# thresholdboard.net
KiCad netlist of a schematic drawn in EAGLE
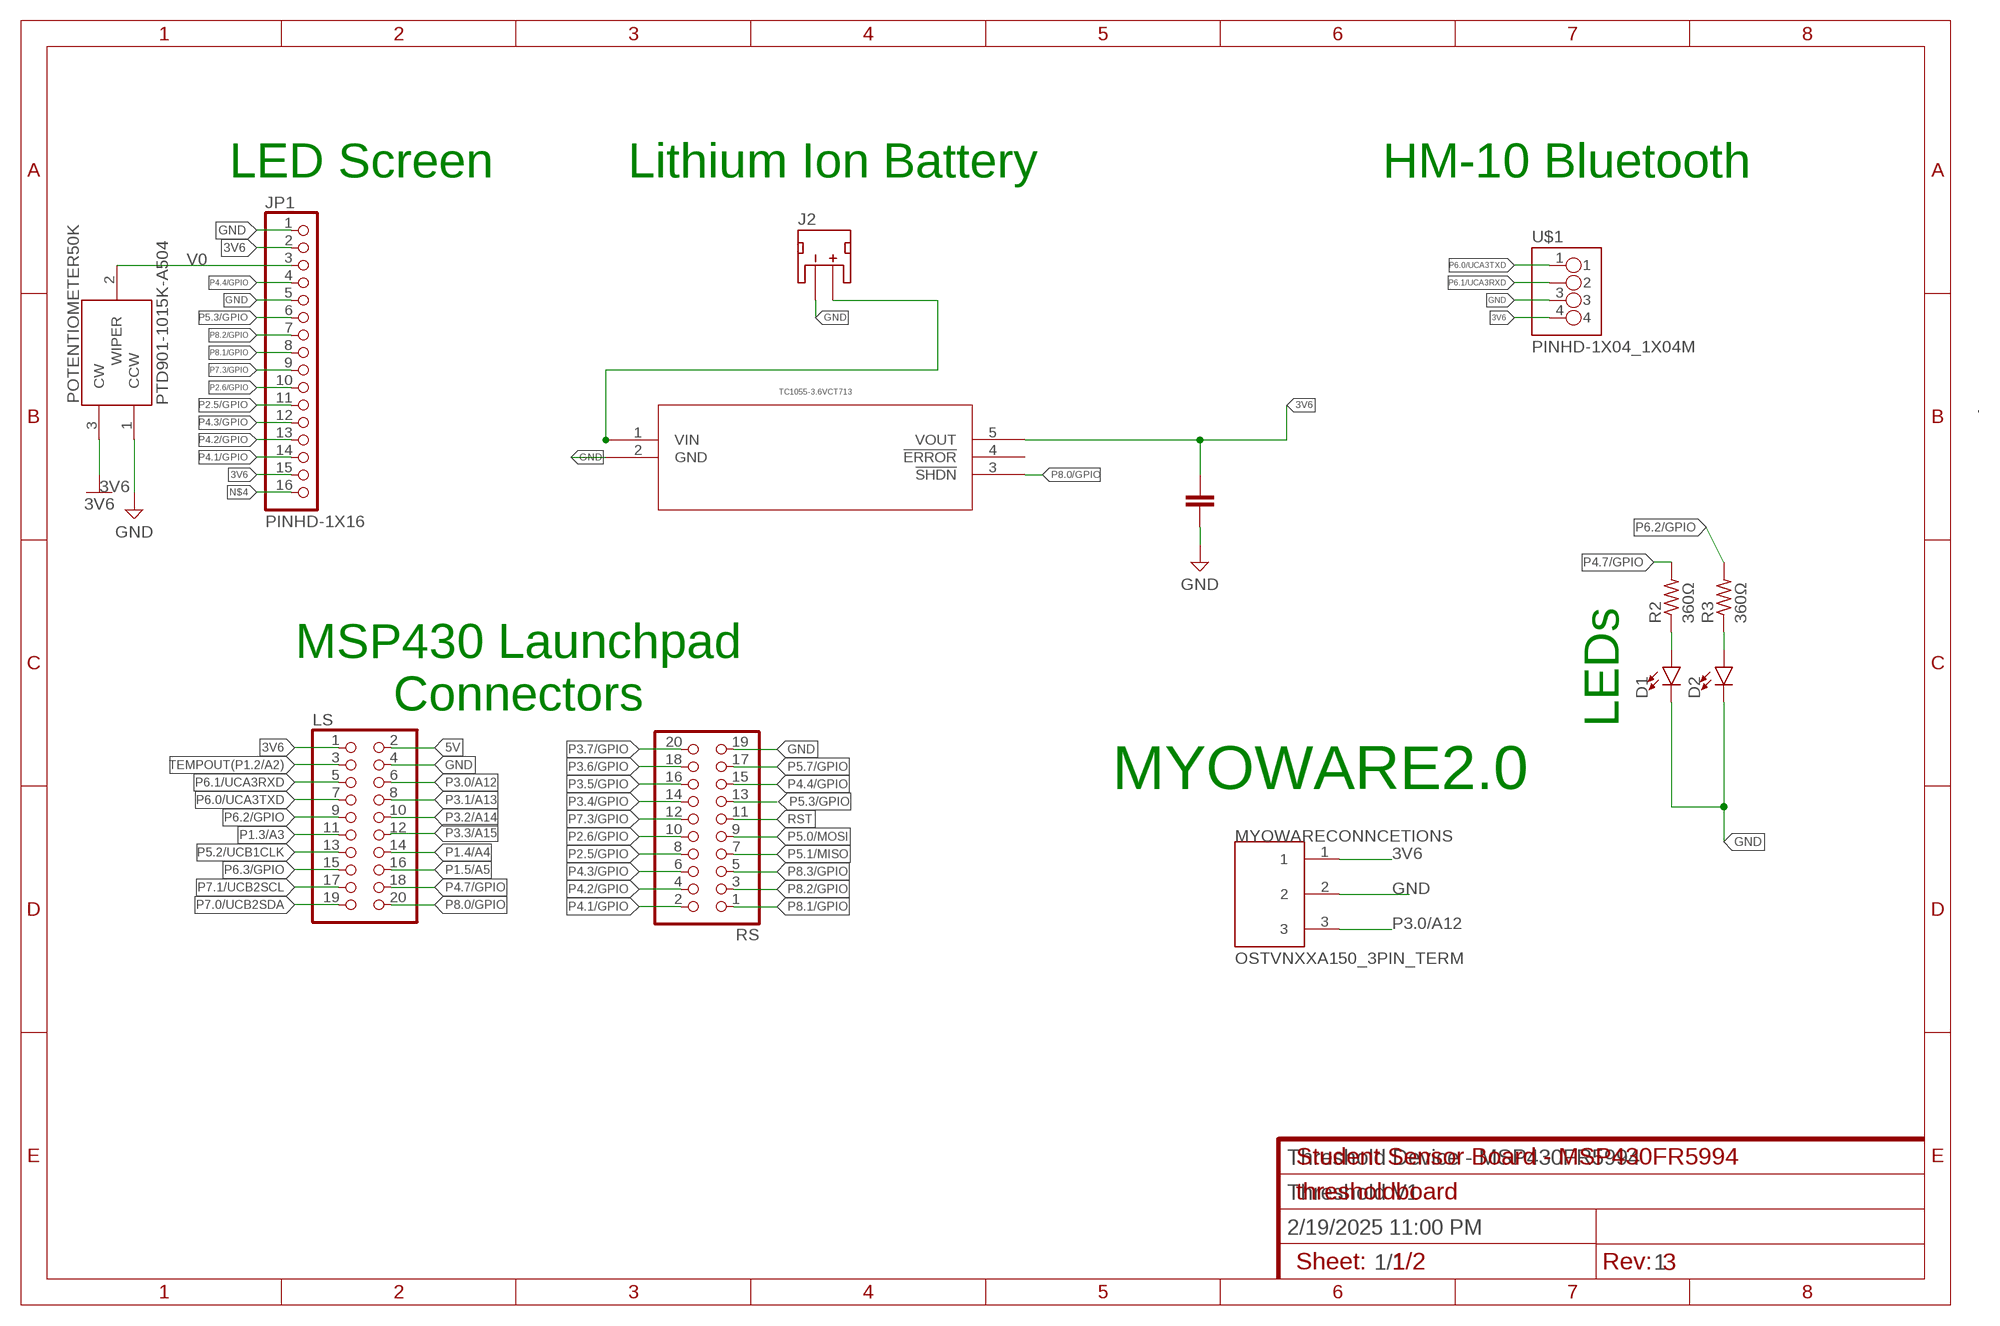
[diagram p0: schematic, sheet 1]

(export (version "E")
  (design (tool "Eeschema 10.0.6"))
  (components
    (comp (ref "C7")
      (value "C_CHIP-0402(1005-METRIC)")
      (footprint "eagle-import:CAPC1005X60")
      (libsource (lib "eagle-import") (part "CCHIP-0402(1005-METRIC)_"))
    )
    (comp (ref "D1")
      (value "LED3MM")
      (footprint "eagle-import:LED_3MM")
      (libsource (lib "eagle-import") (part "LED3MM"))
    )
    (comp (ref "D2")
      (value "LED3MM")
      (footprint "eagle-import:LED_3MM")
      (libsource (lib "eagle-import") (part "LED3MM"))
    )
    (comp (ref "J2")
      (value "JST_2MM_MALE")
      (footprint "eagle-import:JST-2-SMD")
      (libsource (lib "eagle-import") (part "JST_2MM_MALE"))
    )
    (comp (ref "JP1")
      (value "PINHD-1X16")
      (footprint "eagle-import:1X16")
      (libsource (lib "eagle-import") (part "PINHD-1X16"))
    )
    (comp (ref "LS")
      (value "PINHD-2X10")
      (footprint "eagle-import:2X10")
      (libsource (lib "eagle-import") (part "PINHD-2X10"))
    )
    (comp (ref "MYOWARECONNCETIONS")
      (value "OSTVNXXA150_3PIN_TERM")
      (footprint "eagle-import:OSTVNXXA150")
      (libsource (lib "eagle-import") (part "OSTVNXXA150_3PIN_TERM"))
    )
    (comp (ref "POTENTIOMETER50K")
      (value "PTD901-1015K-A504")
      (footprint "eagle-import:PTD9011015KA504")
      (fields (field (name "MOUSER_PART_NUMBER") "652-PTD901-1015KA504"))
      (libsource (lib "eagle-import") (part "PTD901-1015K-A504"))
    )
    (comp (ref "R2")
      (value "360Ω")
      (footprint "eagle-import:R0805")
      (libsource (lib "eagle-import") (part "R-US_R0805"))
    )
    (comp (ref "R3")
      (value "360Ω")
      (footprint "eagle-import:R0805")
      (libsource (lib "eagle-import") (part "R-US_R0805"))
    )
    (comp (ref "RS")
      (value "PINHD-2X10")
      (footprint "eagle-import:2X10")
      (libsource (lib "eagle-import") (part "PINHD-2X10"))
    )
    (comp (ref "U$1")
      (value "PINHD-1X04_1X04M")
      (footprint "eagle-import:1X04")
      (libsource (lib "eagle-import") (part "PINHD-1X04_1X04M"))
    )
    (comp (ref "U1")
      (value "TC1055-3.6VCT713")
      (footprint "eagle-import:SOT-23-5_MC_MCH")
      (fields (field (name "COPYRIGHT") "Copyright (C) 2025 Ultra Librarian. All rights reserved."))
      (libsource (lib "eagle-import") (part "TC1055-3.6VCT713"))
    )
  )
  (nets
    (net (code "1") (name "3V6") (class "Default")
      (node (ref "C7") (pin "1") (pinfunction "1_1") (pintype "passive"))
      (node (ref "JP1") (pin "15") (pinfunction "15_15") (pintype "passive"))
      (node (ref "JP1") (pin "2") (pinfunction "2_2") (pintype "passive"))
      (node (ref "LS") (pin "1") (pinfunction "1_1") (pintype "passive"))
      (node (ref "MYOWARECONNCETIONS") (pin "1") (pinfunction "1_1") (pintype "bidirectional"))
      (node (ref "POTENTIOMETER50K") (pin "3") (pinfunction "CW_3") (pintype "bidirectional"))
      (node (ref "U$1") (pin "4") (pinfunction "4_4") (pintype "bidirectional"))
      (node (ref "U1") (pin "5") (pinfunction "VOUT_5") (pintype "output"))
    )
    (net (code "2") (name "5V") (class "Default")
      (node (ref "LS") (pin "2") (pinfunction "2_2") (pintype "passive"))
    )
    (net (code "3") (name "GND") (class "Default")
      (node (ref "C7") (pin "2") (pinfunction "2_2") (pintype "passive"))
      (node (ref "D1") (pin "K") (pinfunction "C_K") (pintype "passive"))
      (node (ref "D2") (pin "K") (pinfunction "C_K") (pintype "passive"))
      (node (ref "J2") (pin "1") (pinfunction "-_1") (pintype "bidirectional"))
      (node (ref "JP1") (pin "1") (pinfunction "1_1") (pintype "passive"))
      (node (ref "JP1") (pin "5") (pinfunction "5_5") (pintype "passive"))
      (node (ref "LS") (pin "4") (pinfunction "4_4") (pintype "passive"))
      (node (ref "MYOWARECONNCETIONS") (pin "2") (pinfunction "2_2") (pintype "bidirectional"))
      (node (ref "POTENTIOMETER50K") (pin "1") (pinfunction "CCW_1") (pintype "bidirectional"))
      (node (ref "RS") (pin "19") (pinfunction "19_19") (pintype "passive"))
      (node (ref "U$1") (pin "3") (pinfunction "3_3") (pintype "bidirectional"))
      (node (ref "U1") (pin "2") (pinfunction "GND_2") (pintype "power_in"))
    )
    (net (code "4") (name "N$4") (class "Default")
      (node (ref "JP1") (pin "16") (pinfunction "16_16") (pintype "passive"))
    )
    (net (code "5") (name "Net-(D1-PadA)") (class "Default")
      (node (ref "D1") (pin "A") (pinfunction "A_A") (pintype "passive"))
      (node (ref "R2") (pin "1") (pinfunction "1_1") (pintype "passive"))
    )
    (net (code "6") (name "Net-(D2-PadA)") (class "Default")
      (node (ref "D2") (pin "A") (pinfunction "A_A") (pintype "passive"))
      (node (ref "R3") (pin "1") (pinfunction "1_1") (pintype "passive"))
    )
    (net (code "7") (name "Net-(J2-+)") (class "Default")
      (node (ref "J2") (pin "2") (pinfunction "+_2") (pintype "bidirectional"))
      (node (ref "U1") (pin "1") (pinfunction "VIN_1") (pintype "input"))
    )
    (net (code "8") (name "P1.3{slash}A3") (class "Default")
      (node (ref "LS") (pin "11") (pinfunction "11_11") (pintype "passive"))
    )
    (net (code "9") (name "P1.4{slash}A4") (class "Default")
      (node (ref "LS") (pin "14") (pinfunction "14_14") (pintype "passive"))
    )
    (net (code "10") (name "P1.5{slash}A5") (class "Default")
      (node (ref "LS") (pin "16") (pinfunction "16_16") (pintype "passive"))
    )
    (net (code "11") (name "P2.5{slash}GPIO") (class "Default")
      (node (ref "JP1") (pin "11") (pinfunction "11_11") (pintype "passive"))
      (node (ref "RS") (pin "8") (pinfunction "8_8") (pintype "passive"))
    )
    (net (code "12") (name "P2.6{slash}GPIO") (class "Default")
      (node (ref "JP1") (pin "10") (pinfunction "10_10") (pintype "passive"))
      (node (ref "RS") (pin "10") (pinfunction "10_10") (pintype "passive"))
    )
    (net (code "13") (name "P3.0{slash}A12") (class "Default")
      (node (ref "LS") (pin "6") (pinfunction "6_6") (pintype "passive"))
      (node (ref "MYOWARECONNCETIONS") (pin "3") (pinfunction "3_3") (pintype "bidirectional"))
    )
    (net (code "14") (name "P3.1{slash}A13") (class "Default")
      (node (ref "LS") (pin "8") (pinfunction "8_8") (pintype "passive"))
    )
    (net (code "15") (name "P3.2{slash}A14") (class "Default")
      (node (ref "LS") (pin "10") (pinfunction "10_10") (pintype "passive"))
    )
    (net (code "16") (name "P3.3{slash}A15") (class "Default")
      (node (ref "LS") (pin "12") (pinfunction "12_12") (pintype "passive"))
    )
    (net (code "17") (name "P3.4{slash}GPIO") (class "Default")
      (node (ref "RS") (pin "14") (pinfunction "14_14") (pintype "passive"))
    )
    (net (code "18") (name "P3.5{slash}GPIO") (class "Default")
      (node (ref "RS") (pin "16") (pinfunction "16_16") (pintype "passive"))
    )
    (net (code "19") (name "P3.6{slash}GPIO") (class "Default")
      (node (ref "RS") (pin "18") (pinfunction "18_18") (pintype "passive"))
    )
    (net (code "20") (name "P3.7{slash}GPIO") (class "Default")
      (node (ref "RS") (pin "20") (pinfunction "20_20") (pintype "passive"))
    )
    (net (code "21") (name "P4.1{slash}GPIO") (class "Default")
      (node (ref "JP1") (pin "14") (pinfunction "14_14") (pintype "passive"))
      (node (ref "RS") (pin "2") (pinfunction "2_2") (pintype "passive"))
    )
    (net (code "22") (name "P4.2{slash}GPIO") (class "Default")
      (node (ref "JP1") (pin "13") (pinfunction "13_13") (pintype "passive"))
      (node (ref "RS") (pin "4") (pinfunction "4_4") (pintype "passive"))
    )
    (net (code "23") (name "P4.3{slash}GPIO") (class "Default")
      (node (ref "JP1") (pin "12") (pinfunction "12_12") (pintype "passive"))
      (node (ref "RS") (pin "6") (pinfunction "6_6") (pintype "passive"))
    )
    (net (code "24") (name "P4.4{slash}GPIO") (class "Default")
      (node (ref "JP1") (pin "4") (pinfunction "4_4") (pintype "passive"))
      (node (ref "RS") (pin "15") (pinfunction "15_15") (pintype "passive"))
    )
    (net (code "25") (name "P4.7{slash}GPIO") (class "Default")
      (node (ref "LS") (pin "18") (pinfunction "18_18") (pintype "passive"))
      (node (ref "R2") (pin "2") (pinfunction "2_2") (pintype "passive"))
    )
    (net (code "26") (name "P5.0{slash}MOSI") (class "Default")
      (node (ref "RS") (pin "9") (pinfunction "9_9") (pintype "passive"))
    )
    (net (code "27") (name "P5.1{slash}MISO") (class "Default")
      (node (ref "RS") (pin "7") (pinfunction "7_7") (pintype "passive"))
    )
    (net (code "28") (name "P5.2{slash}UCB1CLK") (class "Default")
      (node (ref "LS") (pin "13") (pinfunction "13_13") (pintype "passive"))
    )
    (net (code "29") (name "P5.3{slash}GPIO") (class "Default")
      (node (ref "JP1") (pin "6") (pinfunction "6_6") (pintype "passive"))
      (node (ref "RS") (pin "13") (pinfunction "13_13") (pintype "passive"))
    )
    (net (code "30") (name "P5.7{slash}GPIO") (class "Default")
      (node (ref "RS") (pin "17") (pinfunction "17_17") (pintype "passive"))
    )
    (net (code "31") (name "P6.0{slash}UCA3TXD") (class "Default")
      (node (ref "LS") (pin "7") (pinfunction "7_7") (pintype "passive"))
      (node (ref "U$1") (pin "1") (pinfunction "1_1") (pintype "bidirectional"))
    )
    (net (code "32") (name "P6.1{slash}UCA3RXD") (class "Default")
      (node (ref "LS") (pin "5") (pinfunction "5_5") (pintype "passive"))
      (node (ref "U$1") (pin "2") (pinfunction "2_2") (pintype "bidirectional"))
    )
    (net (code "33") (name "P6.2{slash}GPIO") (class "Default")
      (node (ref "LS") (pin "9") (pinfunction "9_9") (pintype "passive"))
      (node (ref "R3") (pin "2") (pinfunction "2_2") (pintype "passive"))
    )
    (net (code "34") (name "P6.3{slash}GPIO") (class "Default")
      (node (ref "LS") (pin "15") (pinfunction "15_15") (pintype "passive"))
    )
    (net (code "35") (name "P7.0{slash}UCB2SDA") (class "Default")
      (node (ref "LS") (pin "19") (pinfunction "19_19") (pintype "passive"))
    )
    (net (code "36") (name "P7.1{slash}UCB2SCL") (class "Default")
      (node (ref "LS") (pin "17") (pinfunction "17_17") (pintype "passive"))
    )
    (net (code "37") (name "P7.3{slash}GPIO") (class "Default")
      (node (ref "JP1") (pin "9") (pinfunction "9_9") (pintype "passive"))
      (node (ref "RS") (pin "12") (pinfunction "12_12") (pintype "passive"))
    )
    (net (code "38") (name "P8.0{slash}GPIO") (class "Default")
      (node (ref "LS") (pin "20") (pinfunction "20_20") (pintype "passive"))
      (node (ref "U1") (pin "3") (pinfunction "~{SHDN}_3") (pintype "input"))
    )
    (net (code "39") (name "P8.1{slash}GPIO") (class "Default")
      (node (ref "JP1") (pin "8") (pinfunction "8_8") (pintype "passive"))
      (node (ref "RS") (pin "1") (pinfunction "1_1") (pintype "passive"))
    )
    (net (code "40") (name "P8.2{slash}GPIO") (class "Default")
      (node (ref "JP1") (pin "7") (pinfunction "7_7") (pintype "passive"))
      (node (ref "RS") (pin "3") (pinfunction "3_3") (pintype "passive"))
    )
    (net (code "41") (name "P8.3{slash}GPIO") (class "Default")
      (node (ref "RS") (pin "5") (pinfunction "5_5") (pintype "passive"))
    )
    (net (code "42") (name "RST") (class "Default")
      (node (ref "RS") (pin "11") (pinfunction "11_11") (pintype "passive"))
    )
    (net (code "43") (name "TEMPOUT(P1.2{slash}A2)") (class "Default")
      (node (ref "LS") (pin "3") (pinfunction "3_3") (pintype "passive"))
    )
    (net (code "44") (name "V0") (class "Default")
      (node (ref "JP1") (pin "3") (pinfunction "3_3") (pintype "passive"))
      (node (ref "POTENTIOMETER50K") (pin "2") (pinfunction "WIPER_2") (pintype "bidirectional"))
    )
    (net (code "45") (name "unconnected-(J2-PAD1-PadNC1)") (class "Default")
      (node (ref "J2") (pin "NC1") (pinfunction "PAD1_NC1") (pintype "bidirectional"))
    )
    (net (code "46") (name "unconnected-(J2-PAD2-PadNC2)") (class "Default")
      (node (ref "J2") (pin "NC2") (pinfunction "PAD2_NC2") (pintype "bidirectional"))
    )
    (net (code "47") (name "unconnected-(U1-~{ERROR}-Pad4)") (class "Default")
      (node (ref "U1") (pin "4") (pinfunction "~{ERROR}_4") (pintype "output"))
    )
  )
)
